# RES-001_AutoHAT_V2_SD_Adapter_Sub-Board_.net
KiCad netlist of a schematic drawn in Altium Designer
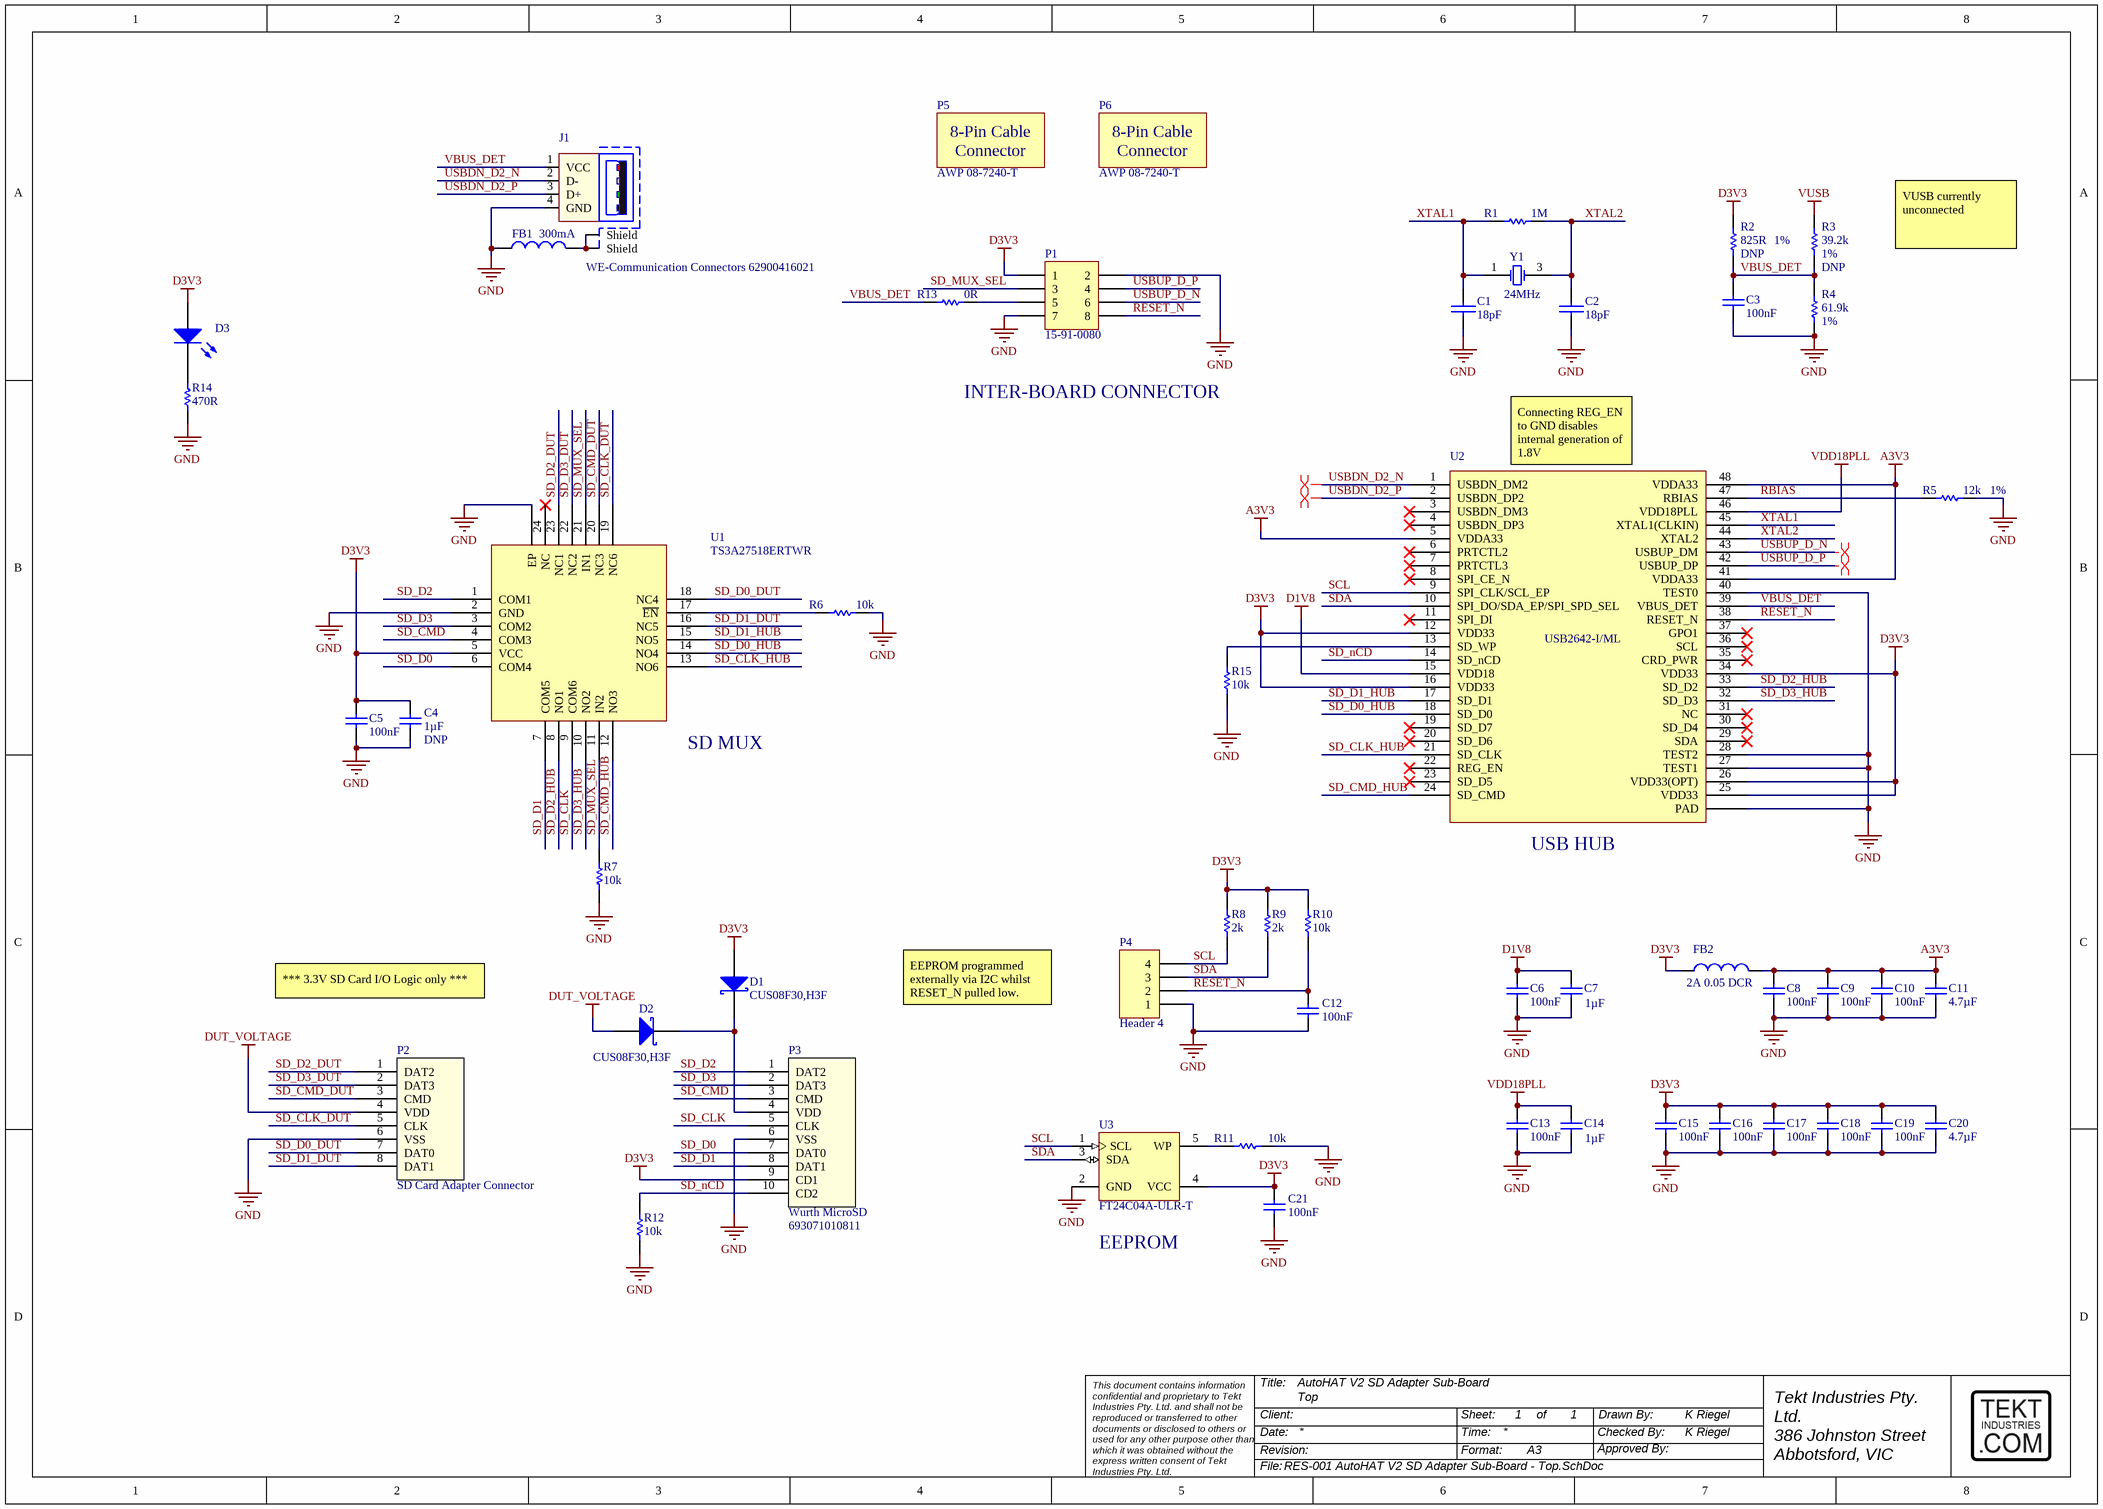
[diagram p0: RES-001 AutoHAT V2 SD Adapter Sub-Board - Top.SchDoc]

(export (version "E")
  (design (tool "Eeschema 10.0.6"))
  (components
    (comp (ref "C1")
      (value "18pF")
      (footprint "0603C - HD")
      (description "18pF ±5% 100V Ceramic Capacitor C0G, NP0 0603 (1608 Metric)")
      (fields
        (field (name "MANUFACTURER") "Samsung Electro-Mechanics America, Inc")
        (field (name "MANUFACTURER PART NO.") "CL10C180JC8NNNC")
        (field (name "CHECKED") "YES")
      )
      (libsource (lib "*") (part "WARDIND3.S01_1uF_14"))
    )
    (comp (ref "C2")
      (value "18pF")
      (footprint "0603C - HD")
      (description "18pF ±5% 100V Ceramic Capacitor C0G, NP0 0603 (1608 Metric)")
      (fields
        (field (name "MANUFACTURER") "Samsung Electro-Mechanics America, Inc")
        (field (name "MANUFACTURER PART NO.") "CL10C180JC8NNNC")
        (field (name "CHECKED") "YES")
      )
      (libsource (lib "*") (part "WARDIND3.S01_1uF_14"))
    )
    (comp (ref "C3")
      (value "100nF")
      (footprint "0402")
      (description "0.10µF 16V Ceramic Capacitor X7R 0402 (1005 Metric) 0.039\" L x 0.020\" W (1.00mm x 0.50mm)")
      (fields
        (field (name "MANUFACTURER") "Samsung Electro-Mechanics America, Inc")
        (field (name "MANUFACTURER PART NO.") "CL05B104KO5NNNC")
        (field (name "CHECKED") "YES")
      )
      (libsource (lib "Miscellaneous Devices") (part "Cap"))
    )
    (comp (ref "C4")
      (value "1µF")
      (footprint "0603C - HD")
      (description "1µF 10V Ceramic Capacitor X7R 0603 (1608 Metric) 0.063\" L x 0.031\" W (1.60mm x 0.80mm)")
      (fields
        (field (name "MANUFACTURER") "Samsung Electro-Mechanics America, Inc")
        (field (name "MANUFACTURER PART NO.") "CL10B105KP8NNNC")
        (field (name "LOAD") "DNP")
        (field (name "CHECKED") "YES")
      )
      (libsource (lib "Miscellaneous Devices") (part "Cap"))
    )
    (comp (ref "C5")
      (value "100nF")
      (footprint "0402")
      (description "0.10µF 16V Ceramic Capacitor X7R 0402 (1005 Metric) 0.039\" L x 0.020\" W (1.00mm x 0.50mm)")
      (fields
        (field (name "MANUFACTURER") "Samsung Electro-Mechanics America, Inc")
        (field (name "MANUFACTURER PART NO.") "CL05B104KO5NNNC")
        (field (name "CHECKED") "YES")
      )
      (libsource (lib "Miscellaneous Devices") (part "Cap"))
    )
    (comp (ref "C6")
      (value "100nF")
      (footprint "0402")
      (description "0.10µF 16V Ceramic Capacitor X7R 0402 (1005 Metric) 0.039\" L x 0.020\" W (1.00mm x 0.50mm)")
      (fields
        (field (name "MANUFACTURER") "Samsung Electro-Mechanics America, Inc")
        (field (name "MANUFACTURER PART NO.") "CL05B104KO5NNNC")
        (field (name "CHECKED") "YES")
      )
      (libsource (lib "Miscellaneous Devices") (part "Cap"))
    )
    (comp (ref "C7")
      (value "1µF")
      (footprint "0603C - HD")
      (description "1µF 10V Ceramic Capacitor X7R 0603 (1608 Metric) 0.063\" L x 0.031\" W (1.60mm x 0.80mm)")
      (fields
        (field (name "MANUFACTURER") "Samsung Electro-Mechanics America, Inc")
        (field (name "MANUFACTURER PART NO.") "CL10B105KP8NNNC")
        (field (name "CHECKED") "YES")
      )
      (libsource (lib "Miscellaneous Devices") (part "Cap"))
    )
    (comp (ref "C8")
      (value "100nF")
      (footprint "0402")
      (description "0.10µF 16V Ceramic Capacitor X7R 0402 (1005 Metric) 0.039\" L x 0.020\" W (1.00mm x 0.50mm)")
      (fields
        (field (name "MANUFACTURER") "Samsung Electro-Mechanics America, Inc")
        (field (name "MANUFACTURER PART NO.") "CL05B104KO5NNNC")
        (field (name "CHECKED") "YES")
      )
      (libsource (lib "Miscellaneous Devices") (part "Cap"))
    )
    (comp (ref "C9")
      (value "100nF")
      (footprint "0402")
      (description "0.10µF 16V Ceramic Capacitor X7R 0402 (1005 Metric) 0.039\" L x 0.020\" W (1.00mm x 0.50mm)")
      (fields
        (field (name "MANUFACTURER") "Samsung Electro-Mechanics America, Inc")
        (field (name "MANUFACTURER PART NO.") "CL05B104KO5NNNC")
        (field (name "CHECKED") "YES")
      )
      (libsource (lib "Miscellaneous Devices") (part "Cap"))
    )
    (comp (ref "C10")
      (value "100nF")
      (footprint "0402")
      (description "0.10µF 16V Ceramic Capacitor X7R 0402 (1005 Metric) 0.039\" L x 0.020\" W (1.00mm x 0.50mm)")
      (fields
        (field (name "MANUFACTURER") "Samsung Electro-Mechanics America, Inc")
        (field (name "MANUFACTURER PART NO.") "CL05B104KO5NNNC")
        (field (name "CHECKED") "YES")
      )
      (libsource (lib "Miscellaneous Devices") (part "Cap"))
    )
    (comp (ref "C11")
      (value "4.7µF")
      (footprint "0603C - HD")
      (description "4.7µF 10V Ceramic Capacitor X5R 0603 (1608 Metric) 0.063\" L x 0.031\" W (1.60mm x 0.80mm)")
      (fields
        (field (name "MANUFACTURER") "Samsung Electro-Mechanics America, Inc")
        (field (name "MANUFACTURER PART NO.") "CL10A475KP8NNNC")
        (field (name "CHECKED") "YES")
      )
      (libsource (lib "Miscellaneous Devices") (part "Cap"))
    )
    (comp (ref "C12")
      (value "100nF")
      (footprint "0402")
      (description "0.10µF 16V Ceramic Capacitor X7R 0402 (1005 Metric) 0.039\" L x 0.020\" W (1.00mm x 0.50mm)")
      (fields
        (field (name "MANUFACTURER") "Samsung Electro-Mechanics America, Inc")
        (field (name "MANUFACTURER PART NO.") "CL05B104KO5NNNC")
        (field (name "CHECKED") "YES")
      )
      (libsource (lib "Miscellaneous Devices") (part "Cap"))
    )
    (comp (ref "C13")
      (value "100nF")
      (footprint "0402")
      (description "0.10µF 16V Ceramic Capacitor X7R 0402 (1005 Metric) 0.039\" L x 0.020\" W (1.00mm x 0.50mm)")
      (fields
        (field (name "MANUFACTURER") "Samsung Electro-Mechanics America, Inc")
        (field (name "MANUFACTURER PART NO.") "CL05B104KO5NNNC")
        (field (name "CHECKED") "YES")
      )
      (libsource (lib "Miscellaneous Devices") (part "Cap"))
    )
    (comp (ref "C14")
      (value "1µF")
      (footprint "0603C - HD")
      (description "1µF 10V Ceramic Capacitor X7R 0603 (1608 Metric) 0.063\" L x 0.031\" W (1.60mm x 0.80mm)")
      (fields
        (field (name "MANUFACTURER") "Samsung Electro-Mechanics America, Inc")
        (field (name "MANUFACTURER PART NO.") "CL10B105KP8NNNC")
        (field (name "CHECKED") "YES")
      )
      (libsource (lib "Miscellaneous Devices") (part "Cap"))
    )
    (comp (ref "C15")
      (value "100nF")
      (footprint "0402")
      (description "0.10µF 16V Ceramic Capacitor X7R 0402 (1005 Metric) 0.039\" L x 0.020\" W (1.00mm x 0.50mm)")
      (fields
        (field (name "MANUFACTURER") "Samsung Electro-Mechanics America, Inc")
        (field (name "MANUFACTURER PART NO.") "CL05B104KO5NNNC")
        (field (name "CHECKED") "YES")
      )
      (libsource (lib "Miscellaneous Devices") (part "Cap"))
    )
    (comp (ref "C16")
      (value "100nF")
      (footprint "0402")
      (description "0.10µF 16V Ceramic Capacitor X7R 0402 (1005 Metric) 0.039\" L x 0.020\" W (1.00mm x 0.50mm)")
      (fields
        (field (name "MANUFACTURER") "Samsung Electro-Mechanics America, Inc")
        (field (name "MANUFACTURER PART NO.") "CL05B104KO5NNNC")
        (field (name "CHECKED") "YES")
      )
      (libsource (lib "Miscellaneous Devices") (part "Cap"))
    )
    (comp (ref "C17")
      (value "100nF")
      (footprint "0402")
      (description "0.10µF 16V Ceramic Capacitor X7R 0402 (1005 Metric) 0.039\" L x 0.020\" W (1.00mm x 0.50mm)")
      (fields
        (field (name "MANUFACTURER") "Samsung Electro-Mechanics America, Inc")
        (field (name "MANUFACTURER PART NO.") "CL05B104KO5NNNC")
        (field (name "CHECKED") "YES")
      )
      (libsource (lib "Miscellaneous Devices") (part "Cap"))
    )
    (comp (ref "C18")
      (value "100nF")
      (footprint "0402")
      (description "0.10µF 16V Ceramic Capacitor X7R 0402 (1005 Metric) 0.039\" L x 0.020\" W (1.00mm x 0.50mm)")
      (fields
        (field (name "MANUFACTURER") "Samsung Electro-Mechanics America, Inc")
        (field (name "MANUFACTURER PART NO.") "CL05B104KO5NNNC")
        (field (name "CHECKED") "YES")
      )
      (libsource (lib "Miscellaneous Devices") (part "Cap"))
    )
    (comp (ref "C19")
      (value "100nF")
      (footprint "0402")
      (description "0.10µF 16V Ceramic Capacitor X7R 0402 (1005 Metric) 0.039\" L x 0.020\" W (1.00mm x 0.50mm)")
      (fields
        (field (name "MANUFACTURER") "Samsung Electro-Mechanics America, Inc")
        (field (name "MANUFACTURER PART NO.") "CL05B104KO5NNNC")
        (field (name "CHECKED") "YES")
      )
      (libsource (lib "Miscellaneous Devices") (part "Cap"))
    )
    (comp (ref "C20")
      (value "4.7µF")
      (footprint "0603C - HD")
      (description "4.7µF 10V Ceramic Capacitor X5R 0603 (1608 Metric) 0.063\" L x 0.031\" W (1.60mm x 0.80mm)")
      (fields
        (field (name "MANUFACTURER") "Samsung Electro-Mechanics America, Inc")
        (field (name "MANUFACTURER PART NO.") "CL10A475KP8NNNC")
        (field (name "CHECKED") "YES")
      )
      (libsource (lib "Miscellaneous Devices") (part "Cap"))
    )
    (comp (ref "C21")
      (value "100nF")
      (footprint "0402")
      (description "0.10µF 16V Ceramic Capacitor X7R 0402 (1005 Metric) 0.039\" L x 0.020\" W (1.00mm x 0.50mm)")
      (fields
        (field (name "MANUFACTURER") "Samsung Electro-Mechanics America, Inc")
        (field (name "MANUFACTURER PART NO.") "CL05B104KO5NNNC")
        (field (name "CHECKED") "YES")
      )
      (libsource (lib "Miscellaneous Devices") (part "Cap"))
    )
    (comp (ref "D1")
      (value "CUS08F30,H3F")
      (footprint "USC")
      (description "Schottky Diode")
      (fields (field (name "MANUFACTURER") "Toshiba Semiconductor and Storage"))
      (libsource (lib "Miscellaneous Devices") (part "D Schottky"))
    )
    (comp (ref "D2")
      (value "CUS08F30,H3F")
      (footprint "USC")
      (description "Schottky Diode")
      (fields (field (name "MANUFACTURER") "Toshiba Semiconductor and Storage"))
      (libsource (lib "Miscellaneous Devices") (part "D Schottky"))
    )
    (comp (ref "D3")
      (value "~")
      (footprint "0603LED - HD")
      (description "Green 571nm LED Indication - Discrete 2V 0603 (1608 Metric)")
      (fields
        (field (name "MANUFACTURER") "Lite-On Inc.")
        (field (name "MANUFACTURER PART NO.") "LTST-C190KGKT")
        (field (name "CHECKED") "YES")
      )
      (libsource (lib "Miscellaneous Devices") (part "LED1"))
    )
    (comp (ref "FB1")
      (value "300mA")
      (footprint "0603L - HD")
      (description "470 Ohm 1 Ferrite Bead 0603 (1608 Metric) 300mA 350 mOhm Max DCR")
      (fields
        (field (name "MANUFACTURER") "Samsung Electro-Mechanics America, Inc")
        (field (name "MANUFACTURER PART NO.") "CIM10J471NC")
        (field (name "CHECKED") "YES")
      )
      (libsource (lib "Miscellaneous Devices") (part "Inductor"))
    )
    (comp (ref "FB2")
      (value "2A 0.05 DCR")
      (footprint "0603L - HD")
      (description "Inductor")
      (fields
        (field (name "MANUFACTURER") "TDK Corporation")
        (field (name "MANUFACTURER PART NO.") "MPZ1608S181ATAH0")
        (field (name "CHECKED") "YES")
      )
      (libsource (lib "Miscellaneous Devices") (part "Inductor"))
    )
    (comp (ref "J1")
      (value "WE-Communication Connectors 62900416021")
      (footprint "62900416021")
      (description "WR-COM USB SMT Type A")
      (fields
        (field (name "MANUFACTURER") "Würth Elektronik eiSos GmbH")
        (field (name "MANUFACTURER PART NO.") "62900416021")
        (field (name "CHECKED") "YES")
      )
      (libsource (lib "WR-COM") (part "WE-Communication Connectors 62900416021"))
    )
    (comp (ref "P1")
      (value "15-91-0080")
      (footprint "15-91-0080")
      (description "Header, 4-Pin, Dual row")
      (fields (field (name "MANUFACTURER") "Molex, LLC"))
      (libsource (lib "Miscellaneous Connectors") (part "Header 4X2"))
    )
    (comp (ref "P2")
      (value "SD Card Adapter Connector")
      (footprint "SD Card")
      (libsource (lib "RES-001 AutoHAT V2 SD Adapter Sub-Board") (part "SD Card Adapter Connector"))
    )
    (comp (ref "P3")
      (value "Wurth MicroSD")
      (footprint "693071010811")
      (fields
        (field (name "MANUFACTURER") "Wurth")
        (field (name "MANUFACTURER PART NO.") "693071010811")
        (field (name "CHECKED") "YES")
      )
      (libsource (lib "Tekt Schematic SYMBOLS") (part "Molex MicroSD"))
    )
    (comp (ref "P4")
      (value "Header 4")
      (footprint "HDR1X4")
      (description "Header, 4-Pin")
      (libsource (lib "Miscellaneous Connectors") (part "Header 4"))
    )
    (comp (ref "P5")
      (value "AWP 08-7240-T")
      (description "8 Position Rectangular Socket Connector IDC Gold")
      (fields (field (name "MANUFACTURER") "Assmann WSW Components"))
      (libsource (lib "RES-001 AutoHAT V2 SD Adapter Sub-Board") (part "AWP 08-7240-T"))
    )
    (comp (ref "P6")
      (value "AWP 08-7240-T")
      (description "8 Position Rectangular Socket Connector IDC Gold")
      (fields (field (name "MANUFACTURER") "Assmann WSW Components"))
      (libsource (lib "RES-001 AutoHAT V2 SD Adapter Sub-Board") (part "AWP 08-7240-T"))
    )
    (comp (ref "R1")
      (value "1M")
      (footprint "0603R - HD")
      (description "RES SMD 1M OHM 5% 1/10W 0603")
      (fields
        (field (name "MANUFACTURER") "Samsung Electro-Mechanics America, Inc")
        (field (name "MANUFACTURER PART NO.") "RC1608J105CS")
        (field (name "CHECKED") "YES")
      )
      (libsource (lib "Miscellaneous Devices") (part "Res1"))
    )
    (comp (ref "R2")
      (value "825R")
      (footprint "0603R - HD")
      (description "825 Ohm ±1% 0.1W, 1/10W Chip Resistor 0603 (1608 Metric) Moisture Resistant Thick Film")
      (fields
        (field (name "MANUFACTURER") "Yageo")
        (field (name "MANUFACTURER PART NO.") "RC0603FR-07825RL")
        (field (name "LOAD") "DNP")
        (field (name "PRECISION") "1%")
        (field (name "CHECKED") "YES")
      )
      (libsource (lib "Miscellaneous Devices") (part "Res1"))
    )
    (comp (ref "R3")
      (value "39.2k")
      (footprint "0603R - HD")
      (description "39.2k Ohm ±1% 0.1W, 1/10W Chip Resistor 0603 (1608 Metric) Moisture Resistant Thick Film")
      (fields
        (field (name "MANUFACTURER") "Yageo")
        (field (name "MANUFACTURER PART NO.") "RC0603FR-0739K2L")
        (field (name "LOAD") "DNP")
        (field (name "PRECISION") "1%")
        (field (name "CHECKED") "YES")
      )
      (libsource (lib "Miscellaneous Devices") (part "Res1"))
    )
    (comp (ref "R4")
      (value "61.9k")
      (footprint "0603R - HD")
      (description "39.2k Ohm ±1% 0.1W, 1/10W Chip Resistor 0603 (1608 Metric) Moisture Resistant Thick Film")
      (fields
        (field (name "MANUFACTURER") "Yageo")
        (field (name "MANUFACTURER PART NO.") "RC0603FR-0761K9L")
        (field (name "PRECISION") "1%")
        (field (name "CHECKED") "YES")
      )
      (libsource (lib "Miscellaneous Devices") (part "Res1"))
    )
    (comp (ref "R5")
      (value "12k")
      (footprint "0603R - HD")
      (description "12k Ohm ±1% 0.1W, 1/10W Chip Resistor 0603 (1608 Metric) Moisture Resistant Thick Film")
      (fields
        (field (name "MANUFACTURER") "Yageo")
        (field (name "MANUFACTURER PART NO.") "RC0603FR-0712KL")
        (field (name "PRECISION") "1%")
        (field (name "CHECKED") "YES")
      )
      (libsource (lib "Miscellaneous Devices") (part "Res1"))
    )
    (comp (ref "R6")
      (value "10k")
      (footprint "0603R - HD")
      (description "RES SMD 10K OHM 5% 1/10W 0603")
      (fields
        (field (name "MANUFACTURER") "Samsung Electro-Mechanics America, Inc")
        (field (name "MANUFACTURER PART NO.") "RC1608J103CS")
        (field (name "CHECKED") "YES")
      )
      (libsource (lib "Miscellaneous Devices") (part "Res1"))
    )
    (comp (ref "R7")
      (value "10k")
      (footprint "0603R - HD")
      (description "RES SMD 10K OHM 5% 1/10W 0603")
      (fields
        (field (name "MANUFACTURER") "Samsung Electro-Mechanics America, Inc")
        (field (name "MANUFACTURER PART NO.") "RC1608J103CS")
        (field (name "CHECKED") "YES")
      )
      (libsource (lib "Miscellaneous Devices") (part "Res1"))
    )
    (comp (ref "R8")
      (value "2k")
      (footprint "0603R - HD")
      (description "RES SMD 2K OHM 5% 1/10W 0603")
      (fields
        (field (name "MANUFACTURER") "Yageo")
        (field (name "MANUFACTURER PART NO.") "RC0603JR-072KL")
        (field (name "CHECKED") "YES")
      )
      (libsource (lib "Miscellaneous Devices") (part "Res1"))
    )
    (comp (ref "R9")
      (value "2k")
      (footprint "0603R - HD")
      (description "RES SMD 2K OHM 5% 1/10W 0603")
      (fields
        (field (name "MANUFACTURER") "Yageo")
        (field (name "MANUFACTURER PART NO.") "RC0603JR-072KL")
        (field (name "CHECKED") "YES")
      )
      (libsource (lib "Miscellaneous Devices") (part "Res1"))
    )
    (comp (ref "R10")
      (value "10k")
      (footprint "0603R - HD")
      (description "RES SMD 10K OHM 5% 1/10W 0603")
      (fields
        (field (name "MANUFACTURER") "Samsung Electro-Mechanics America, Inc")
        (field (name "MANUFACTURER PART NO.") "RC1608J103CS")
        (field (name "CHECKED") "YES")
      )
      (libsource (lib "Miscellaneous Devices") (part "Res1"))
    )
    (comp (ref "R11")
      (value "10k")
      (footprint "0603R - HD")
      (description "RES SMD 10K OHM 5% 1/10W 0603")
      (fields
        (field (name "MANUFACTURER") "Samsung Electro-Mechanics America, Inc")
        (field (name "MANUFACTURER PART NO.") "RC1608J103CS")
        (field (name "CHECKED") "YES")
      )
      (libsource (lib "Miscellaneous Devices") (part "Res1"))
    )
    (comp (ref "R12")
      (value "10k")
      (footprint "0603R - HD")
      (description "RES SMD 10K OHM 5% 1/10W 0603")
      (fields
        (field (name "MANUFACTURER") "Samsung Electro-Mechanics America, Inc")
        (field (name "MANUFACTURER PART NO.") "RC1608J103CS")
        (field (name "CHECKED") "YES")
      )
      (libsource (lib "Miscellaneous Devices") (part "Res1"))
    )
    (comp (ref "R13")
      (value "0R")
      (footprint "0603R - HD")
      (description "RES SMD 0 OHM JUMPER")
      (fields
        (field (name "MANUFACTURER") "Samsung Electro-Mechanics America, Inc")
        (field (name "MANUFACTURER PART NO.") "RC1608J000CS")
        (field (name "CHECKED") "YES")
      )
      (libsource (lib "Miscellaneous Devices") (part "Res1"))
    )
    (comp (ref "R14")
      (value "470R")
      (footprint "0603R - HD")
      (description "RES SMD 470 OHM 5% 1/10W 0603")
      (fields
        (field (name "MANUFACTURER") "Samsung Electro-Mechanics America, Inc")
        (field (name "MANUFACTURER PART NO.") "RC1608J471CS")
        (field (name "CHECKED") "YES")
      )
      (libsource (lib "Miscellaneous Devices") (part "Res1"))
    )
    (comp (ref "R15")
      (value "10k")
      (footprint "1608[0603]")
      (description "RES SMD 10K OHM 5% 1/10W 0603")
      (fields
        (field (name "MANUFACTURER") "Samsung Electro-Mechanics America, Inc")
        (field (name "MANUFACTURER PART NO.") "RC1608J103CS")
        (field (name "CHECKED") "YES")
      )
      (libsource (lib "Miscellaneous Devices") (part "Res1"))
    )
    (comp (ref "U1")
      (value "TS3A27518ERTWR")
      (footprint "QFN-24")
      (description "IC MUX/DEMUX 6X1 24WQFN")
      (fields (field (name "MANUFACTURER") "Texas Instruments"))
      (libsource (lib "RES-001 AutoHAT V2 SD Adapter Sub-Board") (part "TS3A27518E"))
    )
    (comp (ref "U2")
      (value "USB2642-I/ML")
      (footprint "QFN48")
      (description "IC FLASH MEDIA CTLR USB2 48VQFN")
      (fields (field (name "MANUFACTURER") "Microchip Technology") (field (name "CHECKED") "YES"))
      (libsource (lib "RES-001 AutoHAT V2 SD Adapter Sub-Board") (part "USB2642"))
    )
    (comp (ref "U3")
      (value "FT24C04A-ULR-T")
      (footprint "SOT-23-5")
      (description "EEPROM Memory IC 4Kb (512 x 8) I²C 550ns SOT-23-5")
      (fields (field (name "MANUFACTURER") "Fremont Micro Devices USA") (field (name "CHECKED") "YES"))
      (libsource (lib "RES-001 AutoHAT V2 SD Adapter Sub-Board") (part "FT24C04A-ULR-T"))
    )
    (comp (ref "Y1")
      (value "24MHz")
      (footprint "XTAL - 2 x 1.6")
      (description "24MHz ±20ppm Crystal 6pF 150 Ohm -30°C ~ 85°C Surface Mount 4-SMD, No Lead")
      (fields
        (field (name "MANUFACTURER") "Murata Electronics North America")
        (field (name "MANUFACTURER PART NO.") "XRCGB24M000F2P00R0")
        (field (name "CHECKED") "YES")
      )
      (libsource (lib "Miscellaneous Devices") (part "XTAL"))
    )
  )
  (nets
    (net (code "1") (name "/RBIAS") (class "Default")
      (node (ref "R5") (pin "2") (pinfunction "2_2") (pintype "passive"))
      (node (ref "U2") (pin "47") (pinfunction "RBIAS_47") (pintype "passive"))
    )
    (net (code "2") (name "/RESET_N") (class "Default")
      (node (ref "C12") (pin "2") (pinfunction "2_2") (pintype "passive"))
      (node (ref "P1") (pin "8") (pinfunction "8_8") (pintype "passive"))
      (node (ref "P4") (pin "2") (pinfunction "2_2") (pintype "passive"))
      (node (ref "R10") (pin "2") (pinfunction "2_2") (pintype "passive"))
      (node (ref "U2") (pin "38") (pinfunction "RESET_N_38") (pintype "passive"))
    )
    (net (code "3") (name "/SCL") (class "Default")
      (node (ref "P4") (pin "4") (pinfunction "4_4") (pintype "passive"))
      (node (ref "R8") (pin "1") (pinfunction "1_1") (pintype "passive"))
      (node (ref "U2") (pin "9") (pinfunction "SPI_CLK/SCL_EP_9") (pintype "passive"))
      (node (ref "U3") (pin "1") (pinfunction "SCL_1") (pintype "input"))
    )
    (net (code "4") (name "/SDA") (class "Default")
      (node (ref "P4") (pin "3") (pinfunction "3_3") (pintype "passive"))
      (node (ref "R9") (pin "1") (pinfunction "1_1") (pintype "passive"))
      (node (ref "U2") (pin "10") (pinfunction "SPI_DO/SDA_EP/SPI_SPD_SEL_10") (pintype "passive"))
      (node (ref "U3") (pin "3") (pinfunction "SDA_3") (pintype "bidirectional"))
    )
    (net (code "5") (name "/SD_CLK") (class "Default")
      (node (ref "P3") (pin "5") (pinfunction "CLK_5") (pintype "passive"))
      (node (ref "U1") (pin "9") (pinfunction "COM6_9") (pintype "passive"))
    )
    (net (code "6") (name "/SD_CLK_DUT") (class "Default")
      (node (ref "P2") (pin "5") (pinfunction "CLK_5") (pintype "passive"))
      (node (ref "U1") (pin "19") (pinfunction "NC6_19") (pintype "passive"))
    )
    (net (code "7") (name "/SD_CLK_HUB") (class "Default")
      (node (ref "U1") (pin "13") (pinfunction "NO6_13") (pintype "passive"))
      (node (ref "U2") (pin "21") (pinfunction "SD_CLK_21") (pintype "passive"))
    )
    (net (code "8") (name "/SD_CMD") (class "Default")
      (node (ref "P3") (pin "3") (pinfunction "CMD_3") (pintype "passive"))
      (node (ref "U1") (pin "4") (pinfunction "COM3_4") (pintype "passive"))
    )
    (net (code "9") (name "/SD_CMD_DUT") (class "Default")
      (node (ref "P2") (pin "3") (pinfunction "CMD_3") (pintype "passive"))
      (node (ref "U1") (pin "20") (pinfunction "NC3_20") (pintype "passive"))
    )
    (net (code "10") (name "/SD_CMD_HUB") (class "Default")
      (node (ref "U1") (pin "12") (pinfunction "NO3_12") (pintype "passive"))
      (node (ref "U2") (pin "24") (pinfunction "SD_CMD_24") (pintype "passive"))
    )
    (net (code "11") (name "/SD_D0") (class "Default")
      (node (ref "P3") (pin "7") (pinfunction "DAT0_7") (pintype "passive"))
      (node (ref "U1") (pin "6") (pinfunction "COM4_6") (pintype "passive"))
    )
    (net (code "12") (name "/SD_D0_DUT") (class "Default")
      (node (ref "P2") (pin "7") (pinfunction "DAT0_7") (pintype "passive"))
      (node (ref "U1") (pin "18") (pinfunction "NC4_18") (pintype "passive"))
    )
    (net (code "13") (name "/SD_D0_HUB") (class "Default")
      (node (ref "U1") (pin "14") (pinfunction "NO4_14") (pintype "passive"))
      (node (ref "U2") (pin "18") (pinfunction "SD_D0_18") (pintype "passive"))
    )
    (net (code "14") (name "/SD_D1") (class "Default")
      (node (ref "P3") (pin "8") (pinfunction "DAT1_8") (pintype "passive"))
      (node (ref "U1") (pin "7") (pinfunction "COM5_7") (pintype "passive"))
    )
    (net (code "15") (name "/SD_D1_DUT") (class "Default")
      (node (ref "P2") (pin "8") (pinfunction "DAT1_8") (pintype "passive"))
      (node (ref "U1") (pin "16") (pinfunction "NC5_16") (pintype "passive"))
    )
    (net (code "16") (name "/SD_D1_HUB") (class "Default")
      (node (ref "U1") (pin "15") (pinfunction "NO5_15") (pintype "passive"))
      (node (ref "U2") (pin "17") (pinfunction "SD_D1_17") (pintype "passive"))
    )
    (net (code "17") (name "/SD_D2") (class "Default")
      (node (ref "P3") (pin "1") (pinfunction "DAT2_1") (pintype "passive"))
      (node (ref "U1") (pin "1") (pinfunction "COM1_1") (pintype "passive"))
    )
    (net (code "18") (name "/SD_D2_DUT") (class "Default")
      (node (ref "P2") (pin "1") (pinfunction "DAT2_1") (pintype "passive"))
      (node (ref "U1") (pin "23") (pinfunction "NC1_23") (pintype "passive"))
    )
    (net (code "19") (name "/SD_D2_HUB") (class "Default")
      (node (ref "U1") (pin "8") (pinfunction "NO1_8") (pintype "passive"))
      (node (ref "U2") (pin "33") (pinfunction "SD_D2_33") (pintype "passive"))
    )
    (net (code "20") (name "/SD_D3") (class "Default")
      (node (ref "P3") (pin "2") (pinfunction "DAT3_2") (pintype "passive"))
      (node (ref "U1") (pin "3") (pinfunction "COM2_3") (pintype "passive"))
    )
    (net (code "21") (name "/SD_D3_DUT") (class "Default")
      (node (ref "P2") (pin "2") (pinfunction "DAT3_2") (pintype "passive"))
      (node (ref "U1") (pin "22") (pinfunction "NC2_22") (pintype "passive"))
    )
    (net (code "22") (name "/SD_D3_HUB") (class "Default")
      (node (ref "U1") (pin "10") (pinfunction "NO2_10") (pintype "passive"))
      (node (ref "U2") (pin "32") (pinfunction "SD_D3_32") (pintype "passive"))
    )
    (net (code "23") (name "/SD_MUX_SEL") (class "Default")
      (node (ref "P1") (pin "3") (pinfunction "3_3") (pintype "passive"))
      (node (ref "R7") (pin "2") (pinfunction "2_2") (pintype "passive"))
      (node (ref "U1") (pin "11") (pinfunction "IN2_11") (pintype "passive"))
      (node (ref "U1") (pin "21") (pinfunction "IN1_21") (pintype "passive"))
    )
    (net (code "24") (name "/SD_nCD") (class "Default")
      (node (ref "P3") (pin "10") (pinfunction "CD2_10") (pintype "passive"))
      (node (ref "R12") (pin "2") (pinfunction "2_2") (pintype "passive"))
      (node (ref "U2") (pin "14") (pinfunction "SD_nCD_14") (pintype "passive"))
    )
    (net (code "25") (name "/USBDN_D2_N") (class "Default")
      (node (ref "J1") (pin "2") (pinfunction "D-_2") (pintype "passive"))
      (node (ref "U2") (pin "1") (pinfunction "USBDN_DM2_1") (pintype "passive"))
    )
    (net (code "26") (name "/USBDN_D2_P") (class "Default")
      (node (ref "J1") (pin "3") (pinfunction "D+_3") (pintype "passive"))
      (node (ref "U2") (pin "2") (pinfunction "USBDN_DP2_2") (pintype "passive"))
    )
    (net (code "27") (name "/USBUP_D_N") (class "Default")
      (node (ref "P1") (pin "6") (pinfunction "6_6") (pintype "passive"))
      (node (ref "U2") (pin "43") (pinfunction "USBUP_DM_43") (pintype "passive"))
    )
    (net (code "28") (name "/USBUP_D_P") (class "Default")
      (node (ref "P1") (pin "4") (pinfunction "4_4") (pintype "passive"))
      (node (ref "U2") (pin "42") (pinfunction "USBUP_DP_42") (pintype "passive"))
    )
    (net (code "29") (name "/VBUS_DET") (class "Default")
      (node (ref "C3") (pin "2") (pinfunction "2_2") (pintype "passive"))
      (node (ref "J1") (pin "1") (pinfunction "VCC_1") (pintype "passive"))
      (node (ref "R13") (pin "1") (pinfunction "1_1") (pintype "passive"))
      (node (ref "R2") (pin "2") (pinfunction "2_2") (pintype "passive"))
      (node (ref "R3") (pin "2") (pinfunction "2_2") (pintype "passive"))
      (node (ref "R4") (pin "1") (pinfunction "1_1") (pintype "passive"))
      (node (ref "U2") (pin "39") (pinfunction "VBUS_DET_39") (pintype "passive"))
    )
    (net (code "30") (name "/XTAL1") (class "Default")
      (node (ref "C1") (pin "1") (pintype "passive"))
      (node (ref "R1") (pin "1") (pinfunction "1_1") (pintype "passive"))
      (node (ref "U2") (pin "45") (pinfunction "XTAL1(CLKIN)_45") (pintype "passive"))
      (node (ref "Y1") (pin "1") (pinfunction "OSC1_1") (pintype "passive"))
    )
    (net (code "31") (name "/XTAL2") (class "Default")
      (node (ref "C2") (pin "1") (pintype "passive"))
      (node (ref "R1") (pin "2") (pinfunction "2_2") (pintype "passive"))
      (node (ref "U2") (pin "44") (pinfunction "XTAL2_44") (pintype "passive"))
      (node (ref "Y1") (pin "3") (pinfunction "OSC2_3") (pintype "passive"))
    )
    (net (code "32") (name "A3V3") (class "Default")
      (node (ref "C10") (pin "2") (pinfunction "2_2") (pintype "passive"))
      (node (ref "C11") (pin "2") (pinfunction "2_2") (pintype "passive"))
      (node (ref "C8") (pin "2") (pinfunction "2_2") (pintype "passive"))
      (node (ref "C9") (pin "2") (pinfunction "2_2") (pintype "passive"))
      (node (ref "FB2") (pin "2") (pinfunction "2_2") (pintype "passive"))
      (node (ref "U2") (pin "41") (pinfunction "VDDA33_41") (pintype "passive"))
      (node (ref "U2") (pin "48") (pinfunction "VDDA33_48") (pintype "passive"))
      (node (ref "U2") (pin "5") (pinfunction "VDDA33_5") (pintype "passive"))
    )
    (net (code "33") (name "D1V8") (class "Default")
      (node (ref "C6") (pin "2") (pinfunction "2_2") (pintype "passive"))
      (node (ref "C7") (pin "2") (pinfunction "2_2") (pintype "passive"))
      (node (ref "U2") (pin "15") (pinfunction "VDD18_15") (pintype "passive"))
    )
    (net (code "34") (name "D3V3") (class "Default")
      (node (ref "C15") (pin "2") (pinfunction "2_2") (pintype "passive"))
      (node (ref "C16") (pin "2") (pinfunction "2_2") (pintype "passive"))
      (node (ref "C17") (pin "2") (pinfunction "2_2") (pintype "passive"))
      (node (ref "C18") (pin "2") (pinfunction "2_2") (pintype "passive"))
      (node (ref "C19") (pin "2") (pinfunction "2_2") (pintype "passive"))
      (node (ref "C20") (pin "2") (pinfunction "2_2") (pintype "passive"))
      (node (ref "C21") (pin "2") (pinfunction "2_2") (pintype "passive"))
      (node (ref "C4") (pin "2") (pinfunction "2_2") (pintype "passive"))
      (node (ref "C5") (pin "2") (pinfunction "2_2") (pintype "passive"))
      (node (ref "D1") (pin "1") (pinfunction "A_1") (pintype "passive"))
      (node (ref "D3") (pin "1") (pinfunction "A_1") (pintype "passive"))
      (node (ref "FB2") (pin "1") (pinfunction "1_1") (pintype "passive"))
      (node (ref "P1") (pin "1") (pinfunction "1_1") (pintype "passive"))
      (node (ref "P3") (pin "9") (pinfunction "CD1_9") (pintype "passive"))
      (node (ref "R10") (pin "1") (pinfunction "1_1") (pintype "passive"))
      (node (ref "R2") (pin "1") (pinfunction "1_1") (pintype "passive"))
      (node (ref "R8") (pin "2") (pinfunction "2_2") (pintype "passive"))
      (node (ref "R9") (pin "2") (pinfunction "2_2") (pintype "passive"))
      (node (ref "U1") (pin "5") (pinfunction "VCC_5") (pintype "passive"))
      (node (ref "U2") (pin "12") (pinfunction "VDD33_12") (pintype "passive"))
      (node (ref "U2") (pin "16") (pinfunction "VDD33_16") (pintype "passive"))
      (node (ref "U2") (pin "25") (pinfunction "VDD33_25") (pintype "passive"))
      (node (ref "U2") (pin "26") (pinfunction "VDD33(OPT)_26") (pintype "passive"))
      (node (ref "U2") (pin "34") (pinfunction "VDD33_34") (pintype "passive"))
      (node (ref "U3") (pin "4") (pinfunction "VCC_4") (pintype "power_in"))
    )
    (net (code "35") (name "DUT_VOLTAGE") (class "Default")
      (node (ref "D2") (pin "1") (pinfunction "A_1") (pintype "passive"))
      (node (ref "P2") (pin "4") (pinfunction "VDD_4") (pintype "passive"))
    )
    (net (code "36") (name "GND") (class "Default")
      (node (ref "C1") (pin "2") (pintype "passive"))
      (node (ref "C10") (pin "1") (pinfunction "1_1") (pintype "passive"))
      (node (ref "C11") (pin "1") (pinfunction "1_1") (pintype "passive"))
      (node (ref "C12") (pin "1") (pinfunction "1_1") (pintype "passive"))
      (node (ref "C13") (pin "1") (pinfunction "1_1") (pintype "passive"))
      (node (ref "C14") (pin "1") (pinfunction "1_1") (pintype "passive"))
      (node (ref "C15") (pin "1") (pinfunction "1_1") (pintype "passive"))
      (node (ref "C16") (pin "1") (pinfunction "1_1") (pintype "passive"))
      (node (ref "C17") (pin "1") (pinfunction "1_1") (pintype "passive"))
      (node (ref "C18") (pin "1") (pinfunction "1_1") (pintype "passive"))
      (node (ref "C19") (pin "1") (pinfunction "1_1") (pintype "passive"))
      (node (ref "C2") (pin "2") (pintype "passive"))
      (node (ref "C20") (pin "1") (pinfunction "1_1") (pintype "passive"))
      (node (ref "C21") (pin "1") (pinfunction "1_1") (pintype "passive"))
      (node (ref "C3") (pin "1") (pinfunction "1_1") (pintype "passive"))
      (node (ref "C4") (pin "1") (pinfunction "1_1") (pintype "passive"))
      (node (ref "C5") (pin "1") (pinfunction "1_1") (pintype "passive"))
      (node (ref "C6") (pin "1") (pinfunction "1_1") (pintype "passive"))
      (node (ref "C7") (pin "1") (pinfunction "1_1") (pintype "passive"))
      (node (ref "C8") (pin "1") (pinfunction "1_1") (pintype "passive"))
      (node (ref "C9") (pin "1") (pinfunction "1_1") (pintype "passive"))
      (node (ref "FB1") (pin "1") (pinfunction "1_1") (pintype "passive"))
      (node (ref "J1") (pin "4") (pinfunction "GND_4") (pintype "passive"))
      (node (ref "P1") (pin "2") (pinfunction "2_2") (pintype "passive"))
      (node (ref "P1") (pin "7") (pinfunction "7_7") (pintype "passive"))
      (node (ref "P2") (pin "6") (pinfunction "VSS_6") (pintype "passive"))
      (node (ref "P3") (pin "6") (pinfunction "VSS_6") (pintype "passive"))
      (node (ref "P4") (pin "1") (pinfunction "1_1") (pintype "passive"))
      (node (ref "R11") (pin "1") (pinfunction "1_1") (pintype "passive"))
      (node (ref "R12") (pin "1") (pinfunction "1_1") (pintype "passive"))
      (node (ref "R14") (pin "2") (pinfunction "2_2") (pintype "passive"))
      (node (ref "R15") (pin "2") (pinfunction "2_2") (pintype "passive"))
      (node (ref "R4") (pin "2") (pinfunction "2_2") (pintype "passive"))
      (node (ref "R5") (pin "1") (pinfunction "1_1") (pintype "passive"))
      (node (ref "R6") (pin "2") (pinfunction "2_2") (pintype "passive"))
      (node (ref "R7") (pin "1") (pinfunction "1_1") (pintype "passive"))
      (node (ref "U1") (pin "0") (pinfunction "EP_0") (pintype "passive"))
      (node (ref "U1") (pin "2") (pinfunction "GND_2") (pintype "passive"))
      (node (ref "U2") (pin "27") (pinfunction "TEST1_27") (pintype "passive"))
      (node (ref "U2") (pin "28") (pinfunction "TEST2_28") (pintype "passive"))
      (node (ref "U2") (pin "40") (pinfunction "TEST0_40") (pintype "passive"))
      (node (ref "U2") (pin "PAD") (pinfunction "PAD_PAD") (pintype "passive"))
      (node (ref "U3") (pin "2") (pinfunction "GND_2") (pintype "power_in"))
    )
    (net (code "37") (name "Net-(D1-K)") (class "Default")
      (node (ref "D1") (pin "2") (pinfunction "K_2") (pintype "passive"))
      (node (ref "D2") (pin "2") (pinfunction "K_2") (pintype "passive"))
      (node (ref "P3") (pin "4") (pinfunction "VDD_4") (pintype "passive"))
    )
    (net (code "38") (name "Net-(D3-K)") (class "Default")
      (node (ref "D3") (pin "2") (pinfunction "K_2") (pintype "passive"))
      (node (ref "R14") (pin "1") (pinfunction "1_1") (pintype "passive"))
    )
    (net (code "39") (name "Net-(FB1-Pad2)") (class "Default")
      (node (ref "FB1") (pin "2") (pinfunction "2_2") (pintype "passive"))
      (node (ref "J1") (pin "Z1") (pinfunction "Shield_Z1") (pintype "passive"))
      (node (ref "J1") (pin "Z2") (pinfunction "Shield_Z2") (pintype "passive"))
    )
    (net (code "40") (name "Net-(P1-Pad5)") (class "Default")
      (node (ref "P1") (pin "5") (pinfunction "5_5") (pintype "passive"))
      (node (ref "R13") (pin "2") (pinfunction "2_2") (pintype "passive"))
    )
    (net (code "41") (name "Net-(U1-~{EN})") (class "Default")
      (node (ref "R6") (pin "1") (pinfunction "1_1") (pintype "passive"))
      (node (ref "U1") (pin "17") (pinfunction "~{EN}_17") (pintype "passive"))
    )
    (net (code "42") (name "Net-(U2-SD_WP)") (class "Default")
      (node (ref "R15") (pin "1") (pinfunction "1_1") (pintype "passive"))
      (node (ref "U2") (pin "13") (pinfunction "SD_WP_13") (pintype "passive"))
    )
    (net (code "43") (name "Net-(U3-WP)") (class "Default")
      (node (ref "R11") (pin "2") (pinfunction "2_2") (pintype "passive"))
      (node (ref "U3") (pin "5") (pinfunction "WP_5") (pintype "passive"))
    )
    (net (code "44") (name "VDD18PLL") (class "Default")
      (node (ref "C13") (pin "2") (pinfunction "2_2") (pintype "passive"))
      (node (ref "C14") (pin "2") (pinfunction "2_2") (pintype "passive"))
      (node (ref "U2") (pin "46") (pinfunction "VDD18PLL_46") (pintype "passive"))
    )
    (net (code "45") (name "VUSB") (class "Default")
      (node (ref "R3") (pin "1") (pinfunction "1_1") (pintype "passive"))
    )
    (net (code "46") (name "unconnected-(U1-NC-Pad24)") (class "Default")
      (node (ref "U1") (pin "24") (pinfunction "NC_24") (pintype "passive+no_connect"))
    )
    (net (code "47") (name "unconnected-(U2-CRD_PWR-Pad35)") (class "Default")
      (node (ref "U2") (pin "35") (pinfunction "CRD_PWR_35") (pintype "passive+no_connect"))
    )
    (net (code "48") (name "unconnected-(U2-GPO1-Pad37)") (class "Default")
      (node (ref "U2") (pin "37") (pinfunction "GPO1_37") (pintype "passive+no_connect"))
    )
    (net (code "49") (name "unconnected-(U2-NC-Pad31)") (class "Default")
      (node (ref "U2") (pin "31") (pinfunction "NC_31") (pintype "passive+no_connect"))
    )
    (net (code "50") (name "unconnected-(U2-PRTCTL2-Pad6)") (class "Default")
      (node (ref "U2") (pin "6") (pinfunction "PRTCTL2_6") (pintype "passive+no_connect"))
    )
    (net (code "51") (name "unconnected-(U2-PRTCTL3-Pad7)") (class "Default")
      (node (ref "U2") (pin "7") (pinfunction "PRTCTL3_7") (pintype "passive+no_connect"))
    )
    (net (code "52") (name "unconnected-(U2-REG_EN-Pad22)") (class "Default")
      (node (ref "U2") (pin "22") (pinfunction "REG_EN_22") (pintype "passive+no_connect"))
    )
    (net (code "53") (name "unconnected-(U2-SCL-Pad36)") (class "Default")
      (node (ref "U2") (pin "36") (pinfunction "SCL_36") (pintype "passive+no_connect"))
    )
    (net (code "54") (name "unconnected-(U2-SDA-Pad29)") (class "Default")
      (node (ref "U2") (pin "29") (pinfunction "SDA_29") (pintype "passive+no_connect"))
    )
    (net (code "55") (name "unconnected-(U2-SD_D4-Pad30)") (class "Default")
      (node (ref "U2") (pin "30") (pinfunction "SD_D4_30") (pintype "passive+no_connect"))
    )
    (net (code "56") (name "unconnected-(U2-SD_D5-Pad23)") (class "Default")
      (node (ref "U2") (pin "23") (pinfunction "SD_D5_23") (pintype "passive+no_connect"))
    )
    (net (code "57") (name "unconnected-(U2-SD_D6-Pad20)") (class "Default")
      (node (ref "U2") (pin "20") (pinfunction "SD_D6_20") (pintype "passive+no_connect"))
    )
    (net (code "58") (name "unconnected-(U2-SD_D7-Pad19)") (class "Default")
      (node (ref "U2") (pin "19") (pinfunction "SD_D7_19") (pintype "passive+no_connect"))
    )
    (net (code "59") (name "unconnected-(U2-SPI_CE_N-Pad8)") (class "Default")
      (node (ref "U2") (pin "8") (pinfunction "SPI_CE_N_8") (pintype "passive+no_connect"))
    )
    (net (code "60") (name "unconnected-(U2-SPI_DI-Pad11)") (class "Default")
      (node (ref "U2") (pin "11") (pinfunction "SPI_DI_11") (pintype "passive+no_connect"))
    )
    (net (code "61") (name "unconnected-(U2-USBDN_DM3-Pad3)") (class "Default")
      (node (ref "U2") (pin "3") (pinfunction "USBDN_DM3_3") (pintype "passive+no_connect"))
    )
    (net (code "62") (name "unconnected-(U2-USBDN_DP3-Pad4)") (class "Default")
      (node (ref "U2") (pin "4") (pinfunction "USBDN_DP3_4") (pintype "passive+no_connect"))
    )
  )
)
